# DWM1000_2.net
KiCad netlist of a schematic drawn in EAGLE
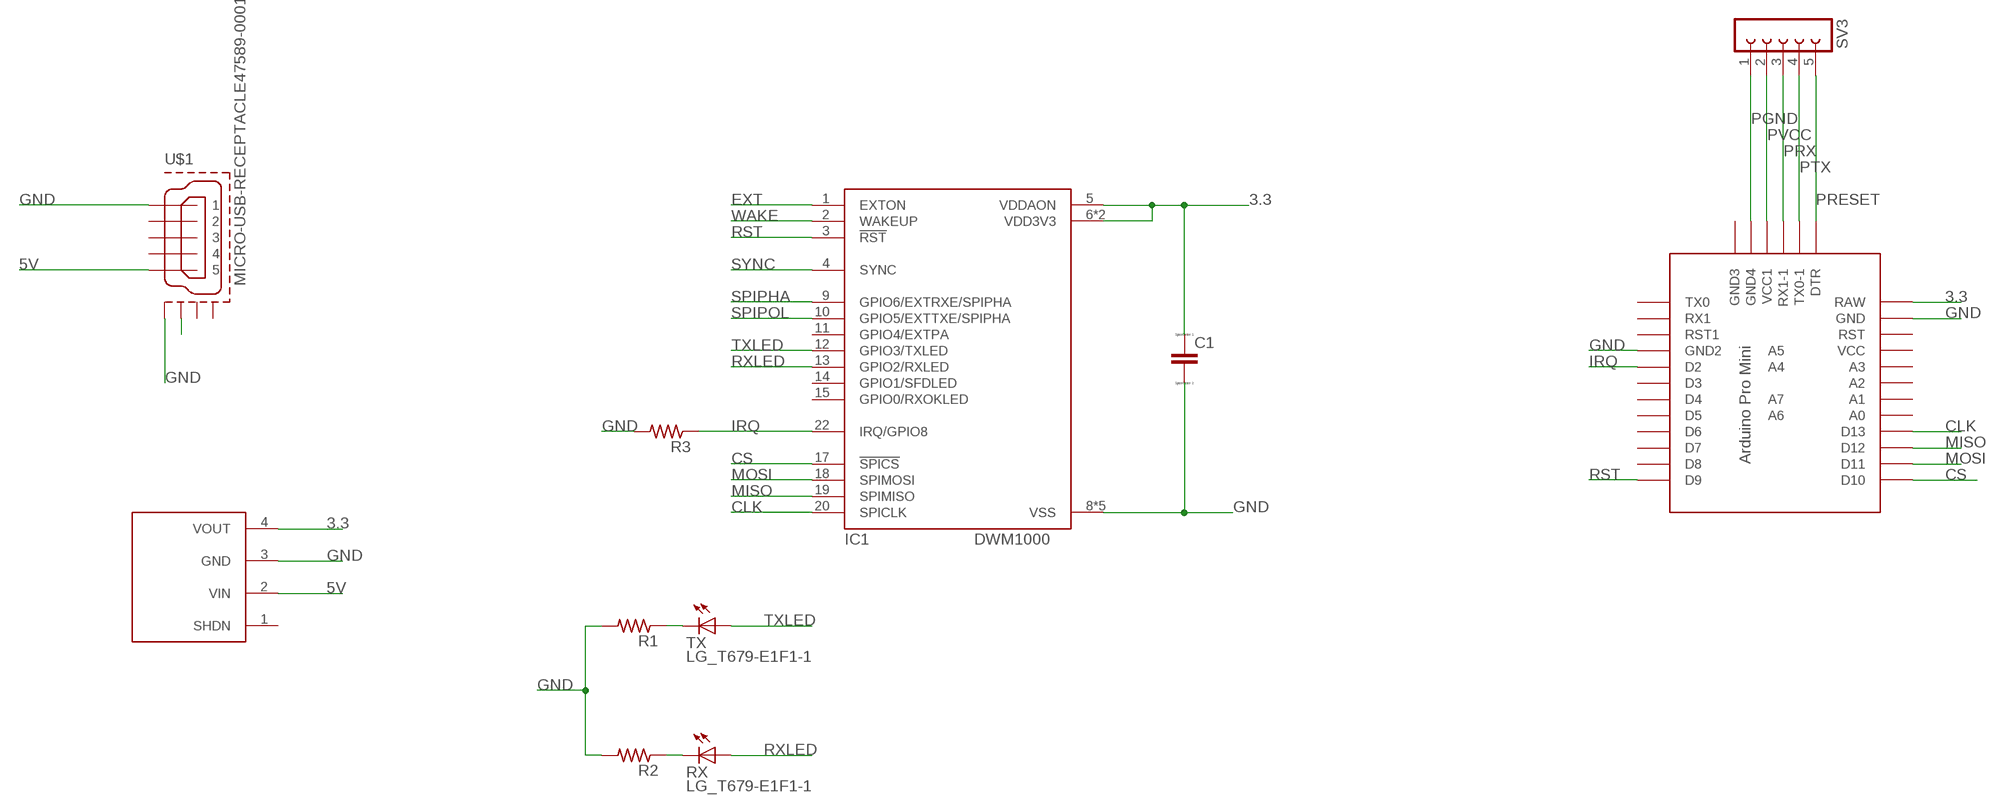
[diagram p0: schematic, sheet 1]

(export (version "E")
  (design (tool "Eeschema 10.0.6"))
  (components
    (comp (ref "C1")
      (value "CC1206")
      (footprint "eagle-import:C1206")
      (libsource (lib "eagle-import") (part "CC1206"))
    )
    (comp (ref "IC1")
      (value "DWM1000")
      (footprint "eagle-import:DWM1000")
      (libsource (lib "eagle-import") (part "DWM1000"))
    )
    (comp (ref "R1")
      (value "R-US_M0805")
      (footprint "eagle-import:M0805")
      (libsource (lib "eagle-import") (part "R-US_M0805"))
    )
    (comp (ref "R2")
      (value "R-US_M0805")
      (footprint "eagle-import:M0805")
      (libsource (lib "eagle-import") (part "R-US_M0805"))
    )
    (comp (ref "R3")
      (value "R-US_M0805")
      (footprint "eagle-import:M0805")
      (libsource (lib "eagle-import") (part "R-US_M0805"))
    )
    (comp (ref "RX")
      (value "LG_T679-E1F1-1")
      (footprint "eagle-import:PLCC2")
      (libsource (lib "eagle-import") (part "_T679-?-1E1F1LG"))
    )
    (comp (ref "SV3")
      (value "FE05-1")
      (footprint "eagle-import:FE05-1")
      (libsource (lib "eagle-import") (part "FE05-1"))
    )
    (comp (ref "TX")
      (value "LG_T679-E1F1-1")
      (footprint "eagle-import:PLCC2")
      (libsource (lib "eagle-import") (part "_T679-?-1E1F1LG"))
    )
    (comp (ref "U$1")
      (value "MICRO-USB-RECEPTACLE47589-0001")
      (footprint "eagle-import:47589-0001")
      (libsource (lib "eagle-import") (part "MICRO-USB-RECEPTACLE47589-0001"))
    )
    (comp (ref "U$2")
      (value "PRO-MINI-2")
      (footprint "eagle-import:PRO-MINI-2")
      (libsource (lib "eagle-import") (part "PRO-MINI-2"))
    )
    (comp (ref "U$3")
      (value "D24V5F3")
      (footprint "eagle-import:D24V5F3")
      (libsource (lib "eagle-import") (part "D24V5F3"))
    )
  )
  (nets
    (net (code "1") (name "/3.3") (class "Default")
      (node (ref "C1") (pin "1") (pinfunction "1_1") (pintype "passive"))
      (node (ref "IC1") (pin "5") (pinfunction "VDDAON_5") (pintype "bidirectional"))
      (node (ref "IC1") (pin "6") (pinfunction "VDD3V3_6") (pintype "bidirectional"))
      (node (ref "IC1") (pin "7") (pinfunction "VDD3V3_7") (pintype "bidirectional"))
      (node (ref "U$2") (pin "RAW") (pinfunction "RAW_RAW") (pintype "bidirectional"))
      (node (ref "U$3") (pin "4") (pinfunction "VOUT_4") (pintype "bidirectional"))
    )
    (net (code "2") (name "/5V") (class "Default")
      (node (ref "U$1") (pin "5") (pinfunction "5_5") (pintype "input"))
      (node (ref "U$3") (pin "2") (pinfunction "VIN_2") (pintype "bidirectional"))
    )
    (net (code "3") (name "/CLK") (class "Default")
      (node (ref "IC1") (pin "20") (pinfunction "SPICLK_20") (pintype "bidirectional"))
      (node (ref "U$2") (pin "D13") (pinfunction "D13_D13") (pintype "bidirectional"))
    )
    (net (code "4") (name "/CS") (class "Default")
      (node (ref "IC1") (pin "17") (pinfunction "~{SPICS}_17") (pintype "bidirectional"))
      (node (ref "U$2") (pin "D10") (pinfunction "D10_D10") (pintype "bidirectional"))
    )
    (net (code "5") (name "/EXT") (class "Default")
      (node (ref "IC1") (pin "1") (pinfunction "EXTON_1") (pintype "bidirectional"))
    )
    (net (code "6") (name "/GND") (class "Default")
      (node (ref "C1") (pin "2") (pinfunction "2_2") (pintype "passive"))
      (node (ref "IC1") (pin "16") (pinfunction "VSS_16") (pintype "bidirectional"))
      (node (ref "IC1") (pin "21") (pinfunction "VSS_21") (pintype "bidirectional"))
      (node (ref "IC1") (pin "23") (pinfunction "VSS_23") (pintype "bidirectional"))
      (node (ref "IC1") (pin "24") (pinfunction "VSS_24") (pintype "bidirectional"))
      (node (ref "IC1") (pin "8") (pinfunction "VSS_8") (pintype "bidirectional"))
      (node (ref "R1") (pin "2") (pinfunction "2_2") (pintype "passive"))
      (node (ref "R2") (pin "2") (pinfunction "2_2") (pintype "passive"))
      (node (ref "R3") (pin "2") (pinfunction "2_2") (pintype "passive"))
      (node (ref "U$1") (pin "1") (pinfunction "1_1") (pintype "input"))
      (node (ref "U$1") (pin "CASING1") (pinfunction "GND1_CASING1") (pintype "bidirectional"))
      (node (ref "U$2") (pin "GND") (pinfunction "GND_GND") (pintype "bidirectional"))
      (node (ref "U$2") (pin "GND1") (pinfunction "GND2_GND1") (pintype "bidirectional"))
      (node (ref "U$3") (pin "3") (pinfunction "GND_3") (pintype "bidirectional"))
    )
    (net (code "7") (name "/IRQ") (class "Default")
      (node (ref "IC1") (pin "22") (pinfunction "IRQ/GPIO8_22") (pintype "bidirectional"))
      (node (ref "R3") (pin "1") (pinfunction "1_1") (pintype "passive"))
      (node (ref "U$2") (pin "D2") (pinfunction "D2_D2") (pintype "bidirectional"))
    )
    (net (code "8") (name "/MISO") (class "Default")
      (node (ref "IC1") (pin "19") (pinfunction "SPIMISO_19") (pintype "bidirectional"))
      (node (ref "U$2") (pin "D12") (pinfunction "D12_D12") (pintype "bidirectional"))
    )
    (net (code "9") (name "/MOSI") (class "Default")
      (node (ref "IC1") (pin "18") (pinfunction "SPIMOSI_18") (pintype "bidirectional"))
      (node (ref "U$2") (pin "D11") (pinfunction "D11_D11") (pintype "bidirectional"))
    )
    (net (code "10") (name "/PGND") (class "Default")
      (node (ref "SV3") (pin "1") (pinfunction "1_1") (pintype "passive"))
      (node (ref "U$2") (pin "GND3") (pinfunction "GND4_GND3") (pintype "bidirectional"))
    )
    (net (code "11") (name "/PRESET") (class "Default")
      (node (ref "SV3") (pin "5") (pinfunction "5_5") (pintype "passive"))
      (node (ref "U$2") (pin "DTR") (pinfunction "DTR_DTR") (pintype "bidirectional"))
    )
    (net (code "12") (name "/PRX") (class "Default")
      (node (ref "SV3") (pin "3") (pinfunction "3_3") (pintype "passive"))
      (node (ref "U$2") (pin "RX1-1") (pinfunction "RX1-1_RX1-1") (pintype "bidirectional"))
    )
    (net (code "13") (name "/PTX") (class "Default")
      (node (ref "SV3") (pin "4") (pinfunction "4_4") (pintype "passive"))
      (node (ref "U$2") (pin "TX0-1") (pinfunction "TX0-1_TX0-1") (pintype "bidirectional"))
    )
    (net (code "14") (name "/PVCC") (class "Default")
      (node (ref "SV3") (pin "2") (pinfunction "2_2") (pintype "passive"))
      (node (ref "U$2") (pin "VCC1") (pinfunction "VCC1_VCC1") (pintype "bidirectional"))
    )
    (net (code "15") (name "/RST") (class "Default")
      (node (ref "IC1") (pin "3") (pinfunction "~{RST}_3") (pintype "bidirectional"))
      (node (ref "U$2") (pin "D9") (pinfunction "D9_D9") (pintype "bidirectional"))
    )
    (net (code "16") (name "/RXLED") (class "Default")
      (node (ref "IC1") (pin "13") (pinfunction "GPIO2/RXLED_13") (pintype "bidirectional"))
      (node (ref "RX") (pin "A") (pinfunction "A_A") (pintype "passive"))
    )
    (net (code "17") (name "/SPIPHA") (class "Default")
      (node (ref "IC1") (pin "9") (pinfunction "GPIO6/EXTRXE/SPIPHA_9") (pintype "bidirectional"))
    )
    (net (code "18") (name "/SPIPOL") (class "Default")
      (node (ref "IC1") (pin "10") (pinfunction "GPIO5/EXTTXE/SPIPHA_10") (pintype "bidirectional"))
    )
    (net (code "19") (name "/SYNC") (class "Default")
      (node (ref "IC1") (pin "4") (pinfunction "SYNC_4") (pintype "bidirectional"))
    )
    (net (code "20") (name "/TXLED") (class "Default")
      (node (ref "IC1") (pin "12") (pinfunction "GPIO3/TXLED_12") (pintype "bidirectional"))
      (node (ref "TX") (pin "A") (pinfunction "A_A") (pintype "passive"))
    )
    (net (code "21") (name "/WAKE") (class "Default")
      (node (ref "IC1") (pin "2") (pinfunction "WAKEUP_2") (pintype "bidirectional"))
    )
    (net (code "22") (name "Net-(R1-Pad1)") (class "Default")
      (node (ref "R1") (pin "1") (pinfunction "1_1") (pintype "passive"))
      (node (ref "TX") (pin "C") (pinfunction "C_C") (pintype "passive"))
    )
    (net (code "23") (name "Net-(R2-Pad1)") (class "Default")
      (node (ref "R2") (pin "1") (pinfunction "1_1") (pintype "passive"))
      (node (ref "RX") (pin "C") (pinfunction "C_C") (pintype "passive"))
    )
    (net (code "24") (name "unconnected-(IC1-GPIO0{slash}RXOKLED-Pad15)") (class "Default")
      (node (ref "IC1") (pin "15") (pinfunction "GPIO0/RXOKLED_15") (pintype "bidirectional"))
    )
    (net (code "25") (name "unconnected-(IC1-GPIO1{slash}SFDLED-Pad14)") (class "Default")
      (node (ref "IC1") (pin "14") (pinfunction "GPIO1/SFDLED_14") (pintype "bidirectional"))
    )
    (net (code "26") (name "unconnected-(IC1-GPIO4{slash}EXTPA-Pad11)") (class "Default")
      (node (ref "IC1") (pin "11") (pinfunction "GPIO4/EXTPA_11") (pintype "bidirectional"))
    )
    (net (code "27") (name "unconnected-(U$1-GND2-PadCASING2)") (class "Default")
      (node (ref "U$1") (pin "CASING2") (pinfunction "GND2_CASING2") (pintype "bidirectional"))
    )
    (net (code "28") (name "unconnected-(U$1-GND3-PadCASING3)") (class "Default")
      (node (ref "U$1") (pin "CASING3") (pinfunction "GND3_CASING3") (pintype "bidirectional"))
    )
    (net (code "29") (name "unconnected-(U$1-GND4-PadCASING4)") (class "Default")
      (node (ref "U$1") (pin "CASING4") (pinfunction "GND4_CASING4") (pintype "bidirectional"))
    )
    (net (code "30") (name "unconnected-(U$1-Pad2)") (class "Default")
      (node (ref "U$1") (pin "2") (pinfunction "2_2") (pintype "input"))
    )
    (net (code "31") (name "unconnected-(U$1-Pad3)") (class "Default")
      (node (ref "U$1") (pin "3") (pinfunction "3_3") (pintype "input"))
    )
    (net (code "32") (name "unconnected-(U$1-Pad4)") (class "Default")
      (node (ref "U$1") (pin "4") (pinfunction "4_4") (pintype "input"))
    )
    (net (code "33") (name "unconnected-(U$2-GND3-PadGND2)") (class "Default")
      (node (ref "U$2") (pin "GND2") (pinfunction "GND3_GND2") (pintype "bidirectional"))
    )
    (net (code "34") (name "unconnected-(U$2-PadA0)") (class "Default")
      (node (ref "U$2") (pin "A0") (pinfunction "A0_A0") (pintype "bidirectional"))
    )
    (net (code "35") (name "unconnected-(U$2-PadA1)") (class "Default")
      (node (ref "U$2") (pin "A1") (pinfunction "A1_A1") (pintype "bidirectional"))
    )
    (net (code "36") (name "unconnected-(U$2-PadA2)") (class "Default")
      (node (ref "U$2") (pin "A2") (pinfunction "A2_A2") (pintype "bidirectional"))
    )
    (net (code "37") (name "unconnected-(U$2-PadA3)") (class "Default")
      (node (ref "U$2") (pin "A3") (pinfunction "A3_A3") (pintype "bidirectional"))
    )
    (net (code "38") (name "unconnected-(U$2-PadA4)") (class "Default")
      (node (ref "U$2") (pin "A4") (pinfunction "A4_A4") (pintype "bidirectional"))
    )
    (net (code "39") (name "unconnected-(U$2-PadA5)") (class "Default")
      (node (ref "U$2") (pin "A5") (pinfunction "A5_A5") (pintype "bidirectional"))
    )
    (net (code "40") (name "unconnected-(U$2-PadA6)") (class "Default")
      (node (ref "U$2") (pin "A6") (pinfunction "A6_A6") (pintype "bidirectional"))
    )
    (net (code "41") (name "unconnected-(U$2-PadA7)") (class "Default")
      (node (ref "U$2") (pin "A7") (pinfunction "A7_A7") (pintype "bidirectional"))
    )
    (net (code "42") (name "unconnected-(U$2-PadD3)") (class "Default")
      (node (ref "U$2") (pin "D3") (pinfunction "D3_D3") (pintype "bidirectional"))
    )
    (net (code "43") (name "unconnected-(U$2-PadD4)") (class "Default")
      (node (ref "U$2") (pin "D4") (pinfunction "D4_D4") (pintype "bidirectional"))
    )
    (net (code "44") (name "unconnected-(U$2-PadD5)") (class "Default")
      (node (ref "U$2") (pin "D5") (pinfunction "D5_D5") (pintype "bidirectional"))
    )
    (net (code "45") (name "unconnected-(U$2-PadD6)") (class "Default")
      (node (ref "U$2") (pin "D6") (pinfunction "D6_D6") (pintype "bidirectional"))
    )
    (net (code "46") (name "unconnected-(U$2-PadD7)") (class "Default")
      (node (ref "U$2") (pin "D7") (pinfunction "D7_D7") (pintype "bidirectional"))
    )
    (net (code "47") (name "unconnected-(U$2-PadD8)") (class "Default")
      (node (ref "U$2") (pin "D8") (pinfunction "D8_D8") (pintype "bidirectional"))
    )
    (net (code "48") (name "unconnected-(U$2-PadRST)") (class "Default")
      (node (ref "U$2") (pin "RST") (pinfunction "RST_RST") (pintype "bidirectional"))
    )
    (net (code "49") (name "unconnected-(U$2-PadRST1)") (class "Default")
      (node (ref "U$2") (pin "RST1") (pinfunction "RST1_RST1") (pintype "bidirectional"))
    )
    (net (code "50") (name "unconnected-(U$2-PadRX1)") (class "Default")
      (node (ref "U$2") (pin "RX1") (pinfunction "RX1_RX1") (pintype "bidirectional"))
    )
    (net (code "51") (name "unconnected-(U$2-PadTX0)") (class "Default")
      (node (ref "U$2") (pin "TX0") (pinfunction "TX0_TX0") (pintype "bidirectional"))
    )
    (net (code "52") (name "unconnected-(U$2-PadVCC)") (class "Default")
      (node (ref "U$2") (pin "VCC") (pinfunction "VCC_VCC") (pintype "bidirectional"))
    )
    (net (code "53") (name "unconnected-(U$3-SHDN-Pad1)") (class "Default")
      (node (ref "U$3") (pin "1") (pinfunction "SHDN_1") (pintype "bidirectional"))
    )
  )
)
